# rasp_universal.net
KiCad netlist of a schematic drawn in EAGLE
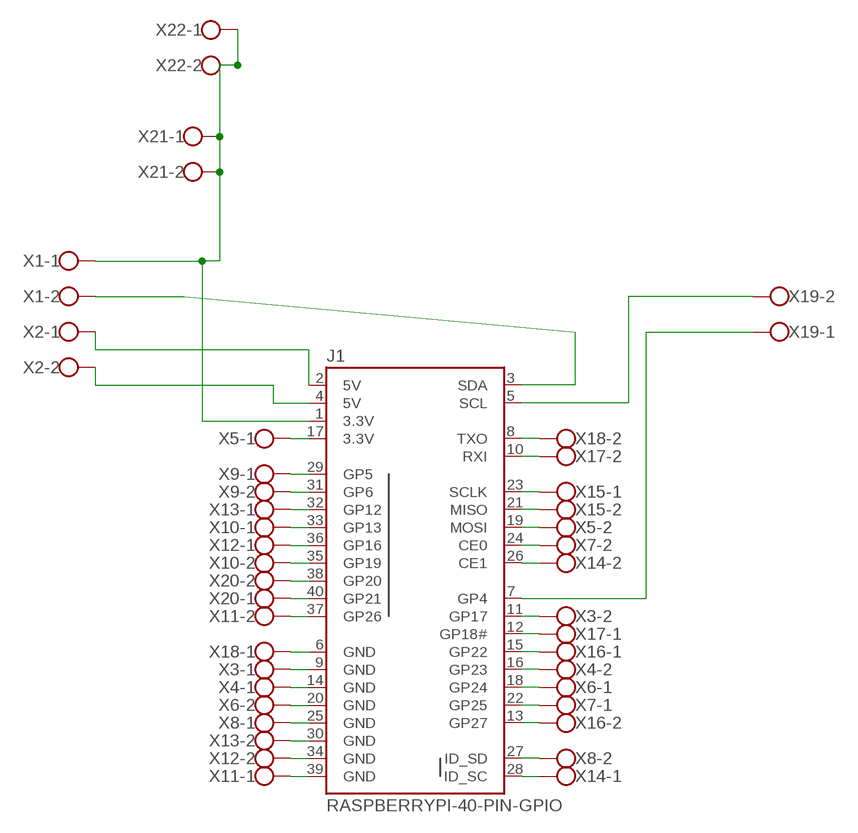
[diagram p0: schematic, sheet 1]

(export (version "E")
  (design (tool "Eeschema 10.0.6"))
  (components
    (comp (ref "J1")
      (value "RASPBERRYPI-40-PIN-GPIO")
      (footprint "eagle-import:2X20-SHROUDED")
      (libsource (lib "eagle-import") (part "RASPBERRYPI-40-PIN-GPIO"))
    )
    (comp (ref "X1")
      (value "W237-102")
      (footprint "eagle-import:W237-102")
      (fields (field (name "MPN") "237-102"))
      (libsource (lib "eagle-import") (part "W237-102"))
    )
    (comp (ref "X2")
      (value "W237-102")
      (footprint "eagle-import:W237-102")
      (fields (field (name "MPN") "237-102"))
      (libsource (lib "eagle-import") (part "W237-102"))
    )
    (comp (ref "X3")
      (value "W237-102")
      (footprint "eagle-import:W237-102")
      (fields (field (name "MPN") "237-102"))
      (libsource (lib "eagle-import") (part "W237-102"))
    )
    (comp (ref "X4")
      (value "W237-102")
      (footprint "eagle-import:W237-102")
      (fields (field (name "MPN") "237-102"))
      (libsource (lib "eagle-import") (part "W237-102"))
    )
    (comp (ref "X5")
      (value "W237-102")
      (footprint "eagle-import:W237-102")
      (fields (field (name "MPN") "237-102"))
      (libsource (lib "eagle-import") (part "W237-102"))
    )
    (comp (ref "X6")
      (value "W237-102")
      (footprint "eagle-import:W237-102")
      (fields (field (name "MPN") "237-102"))
      (libsource (lib "eagle-import") (part "W237-102"))
    )
    (comp (ref "X7")
      (value "W237-102")
      (footprint "eagle-import:W237-102")
      (fields (field (name "MPN") "237-102"))
      (libsource (lib "eagle-import") (part "W237-102"))
    )
    (comp (ref "X8")
      (value "W237-102")
      (footprint "eagle-import:W237-102")
      (fields (field (name "MPN") "237-102"))
      (libsource (lib "eagle-import") (part "W237-102"))
    )
    (comp (ref "X9")
      (value "W237-102")
      (footprint "eagle-import:W237-102")
      (fields (field (name "MPN") "237-102"))
      (libsource (lib "eagle-import") (part "W237-102"))
    )
    (comp (ref "X10")
      (value "W237-102")
      (footprint "eagle-import:W237-102")
      (fields (field (name "MPN") "237-102"))
      (libsource (lib "eagle-import") (part "W237-102"))
    )
    (comp (ref "X11")
      (value "W237-102")
      (footprint "eagle-import:W237-102")
      (fields (field (name "MPN") "237-102"))
      (libsource (lib "eagle-import") (part "W237-102"))
    )
    (comp (ref "X12")
      (value "W237-102")
      (footprint "eagle-import:W237-102")
      (fields (field (name "MPN") "237-102"))
      (libsource (lib "eagle-import") (part "W237-102"))
    )
    (comp (ref "X13")
      (value "W237-102")
      (footprint "eagle-import:W237-102")
      (fields (field (name "MPN") "237-102"))
      (libsource (lib "eagle-import") (part "W237-102"))
    )
    (comp (ref "X14")
      (value "W237-102")
      (footprint "eagle-import:W237-102")
      (fields (field (name "MPN") "237-102"))
      (libsource (lib "eagle-import") (part "W237-102"))
    )
    (comp (ref "X15")
      (value "W237-102")
      (footprint "eagle-import:W237-102")
      (fields (field (name "MPN") "237-102"))
      (libsource (lib "eagle-import") (part "W237-102"))
    )
    (comp (ref "X16")
      (value "W237-102")
      (footprint "eagle-import:W237-102")
      (fields (field (name "MPN") "237-102"))
      (libsource (lib "eagle-import") (part "W237-102"))
    )
    (comp (ref "X17")
      (value "W237-102")
      (footprint "eagle-import:W237-102")
      (fields (field (name "MPN") "237-102"))
      (libsource (lib "eagle-import") (part "W237-102"))
    )
    (comp (ref "X18")
      (value "W237-102")
      (footprint "eagle-import:W237-102")
      (fields (field (name "MPN") "237-102"))
      (libsource (lib "eagle-import") (part "W237-102"))
    )
    (comp (ref "X19")
      (value "W237-102")
      (footprint "eagle-import:W237-102")
      (fields (field (name "MPN") "237-102"))
      (libsource (lib "eagle-import") (part "W237-102"))
    )
    (comp (ref "X20")
      (value "W237-102")
      (footprint "eagle-import:W237-102")
      (fields (field (name "MPN") "237-102"))
      (libsource (lib "eagle-import") (part "W237-102"))
    )
    (comp (ref "X21")
      (value "W237-102")
      (footprint "eagle-import:W237-102")
      (fields (field (name "MPN") "237-102"))
      (libsource (lib "eagle-import") (part "W237-102"))
    )
    (comp (ref "X22")
      (value "W237-102")
      (footprint "eagle-import:W237-102")
      (fields (field (name "MPN") "237-102"))
      (libsource (lib "eagle-import") (part "W237-102"))
    )
  )
  (nets
    (net (code "1") (name "Net-(J1-CE0)") (class "Default")
      (node (ref "J1") (pin "24") (pinfunction "CE0_24") (pintype "output"))
      (node (ref "X7") (pin "2") (pinfunction "KL_2") (pintype "passive"))
    )
    (net (code "2") (name "Net-(J1-CE1)") (class "Default")
      (node (ref "J1") (pin "26") (pinfunction "CE1_26") (pintype "output"))
      (node (ref "X14") (pin "2") (pinfunction "KL_2") (pintype "passive"))
    )
    (net (code "3") (name "Net-(J1-GP4)") (class "Default")
      (node (ref "J1") (pin "7") (pinfunction "GP4_7") (pintype "bidirectional"))
      (node (ref "X19") (pin "1") (pinfunction "KL_1") (pintype "passive"))
    )
    (net (code "4") (name "Net-(J1-GP5)") (class "Default")
      (node (ref "J1") (pin "29") (pinfunction "GP5_29") (pintype "bidirectional"))
      (node (ref "X9") (pin "1") (pinfunction "KL_1") (pintype "passive"))
    )
    (net (code "5") (name "Net-(J1-GP6)") (class "Default")
      (node (ref "J1") (pin "31") (pinfunction "GP6_31") (pintype "bidirectional"))
      (node (ref "X9") (pin "2") (pinfunction "KL_2") (pintype "passive"))
    )
    (net (code "6") (name "Net-(J1-GP12)") (class "Default")
      (node (ref "J1") (pin "32") (pinfunction "GP12_32") (pintype "bidirectional"))
      (node (ref "X13") (pin "1") (pinfunction "KL_1") (pintype "passive"))
    )
    (net (code "7") (name "Net-(J1-GP13)") (class "Default")
      (node (ref "J1") (pin "33") (pinfunction "GP13_33") (pintype "bidirectional"))
      (node (ref "X10") (pin "1") (pinfunction "KL_1") (pintype "passive"))
    )
    (net (code "8") (name "Net-(J1-GP16)") (class "Default")
      (node (ref "J1") (pin "36") (pinfunction "GP16_36") (pintype "bidirectional"))
      (node (ref "X12") (pin "1") (pinfunction "KL_1") (pintype "passive"))
    )
    (net (code "9") (name "Net-(J1-GP17)") (class "Default")
      (node (ref "J1") (pin "11") (pinfunction "GP17_11") (pintype "bidirectional"))
      (node (ref "X3") (pin "2") (pinfunction "KL_2") (pintype "passive"))
    )
    (net (code "10") (name "Net-(J1-GP18#)") (class "Default")
      (node (ref "J1") (pin "12") (pinfunction "GP18#_12") (pintype "bidirectional"))
      (node (ref "X17") (pin "1") (pinfunction "KL_1") (pintype "passive"))
    )
    (net (code "11") (name "Net-(J1-GP19)") (class "Default")
      (node (ref "J1") (pin "35") (pinfunction "GP19_35") (pintype "bidirectional"))
      (node (ref "X10") (pin "2") (pinfunction "KL_2") (pintype "passive"))
    )
    (net (code "12") (name "Net-(J1-GP20)") (class "Default")
      (node (ref "J1") (pin "38") (pinfunction "GP20_38") (pintype "bidirectional"))
      (node (ref "X20") (pin "2") (pinfunction "KL_2") (pintype "passive"))
    )
    (net (code "13") (name "Net-(J1-GP21)") (class "Default")
      (node (ref "J1") (pin "40") (pinfunction "GP21_40") (pintype "bidirectional"))
      (node (ref "X20") (pin "1") (pinfunction "KL_1") (pintype "passive"))
    )
    (net (code "14") (name "Net-(J1-GP22)") (class "Default")
      (node (ref "J1") (pin "15") (pinfunction "GP22_15") (pintype "bidirectional"))
      (node (ref "X16") (pin "1") (pinfunction "KL_1") (pintype "passive"))
    )
    (net (code "15") (name "Net-(J1-GP23)") (class "Default")
      (node (ref "J1") (pin "16") (pinfunction "GP23_16") (pintype "bidirectional"))
      (node (ref "X4") (pin "2") (pinfunction "KL_2") (pintype "passive"))
    )
    (net (code "16") (name "Net-(J1-GP24)") (class "Default")
      (node (ref "J1") (pin "18") (pinfunction "GP24_18") (pintype "bidirectional"))
      (node (ref "X6") (pin "1") (pinfunction "KL_1") (pintype "passive"))
    )
    (net (code "17") (name "Net-(J1-GP25)") (class "Default")
      (node (ref "J1") (pin "22") (pinfunction "GP25_22") (pintype "bidirectional"))
      (node (ref "X7") (pin "1") (pinfunction "KL_1") (pintype "passive"))
    )
    (net (code "18") (name "Net-(J1-GP26)") (class "Default")
      (node (ref "J1") (pin "37") (pinfunction "GP26_37") (pintype "bidirectional"))
      (node (ref "X11") (pin "2") (pinfunction "KL_2") (pintype "passive"))
    )
    (net (code "19") (name "Net-(J1-GP27)") (class "Default")
      (node (ref "J1") (pin "13") (pinfunction "GP27_13") (pintype "bidirectional"))
      (node (ref "X16") (pin "2") (pinfunction "KL_2") (pintype "passive"))
    )
    (net (code "20") (name "Net-(J1-ID_SC)") (class "Default")
      (node (ref "J1") (pin "28") (pinfunction "ID_SC_28") (pintype "bidirectional"))
      (node (ref "X14") (pin "1") (pinfunction "KL_1") (pintype "passive"))
    )
    (net (code "21") (name "Net-(J1-ID_SD)") (class "Default")
      (node (ref "J1") (pin "27") (pinfunction "ID_SD_27") (pintype "bidirectional"))
      (node (ref "X8") (pin "2") (pinfunction "KL_2") (pintype "passive"))
    )
    (net (code "22") (name "Net-(J1-MISO)") (class "Default")
      (node (ref "J1") (pin "21") (pinfunction "MISO_21") (pintype "input"))
      (node (ref "X15") (pin "2") (pinfunction "KL_2") (pintype "passive"))
    )
    (net (code "23") (name "Net-(J1-MOSI)") (class "Default")
      (node (ref "J1") (pin "19") (pinfunction "MOSI_19") (pintype "output"))
      (node (ref "X5") (pin "2") (pinfunction "KL_2") (pintype "passive"))
    )
    (net (code "24") (name "Net-(J1-RXI)") (class "Default")
      (node (ref "J1") (pin "10") (pinfunction "RXI_10") (pintype "input"))
      (node (ref "X17") (pin "2") (pinfunction "KL_2") (pintype "passive"))
    )
    (net (code "25") (name "Net-(J1-SCL)") (class "Default")
      (node (ref "J1") (pin "5") (pinfunction "SCL_5") (pintype "bidirectional"))
      (node (ref "X19") (pin "2") (pinfunction "KL_2") (pintype "passive"))
    )
    (net (code "26") (name "Net-(J1-SCLK)") (class "Default")
      (node (ref "J1") (pin "23") (pinfunction "SCLK_23") (pintype "output"))
      (node (ref "X15") (pin "1") (pinfunction "KL_1") (pintype "passive"))
    )
    (net (code "27") (name "Net-(J1-SDA)") (class "Default")
      (node (ref "J1") (pin "3") (pinfunction "SDA_3") (pintype "bidirectional"))
      (node (ref "X1") (pin "2") (pinfunction "KL_2") (pintype "passive"))
    )
    (net (code "28") (name "Net-(J1-TXO)") (class "Default")
      (node (ref "J1") (pin "8") (pinfunction "TXO_8") (pintype "output"))
      (node (ref "X18") (pin "2") (pinfunction "KL_2") (pintype "passive"))
    )
    (net (code "29") (name "Net-(X1A-KL)") (class "Default")
      (node (ref "J1") (pin "1") (pinfunction "3.3V_1") (pintype "power_in"))
      (node (ref "X1") (pin "1") (pinfunction "KL_1") (pintype "passive"))
      (node (ref "X21") (pin "1") (pinfunction "KL_1") (pintype "passive"))
      (node (ref "X21") (pin "2") (pinfunction "KL_2") (pintype "passive"))
      (node (ref "X22") (pin "1") (pinfunction "KL_1") (pintype "passive"))
      (node (ref "X22") (pin "2") (pinfunction "KL_2") (pintype "passive"))
    )
    (net (code "30") (name "Net-(X2A-KL)") (class "Default")
      (node (ref "J1") (pin "2") (pinfunction "5V_2") (pintype "power_in"))
      (node (ref "X2") (pin "1") (pinfunction "KL_1") (pintype "passive"))
    )
    (net (code "31") (name "Net-(X2B-KL)") (class "Default")
      (node (ref "J1") (pin "4") (pinfunction "5V_4") (pintype "power_in"))
      (node (ref "X2") (pin "2") (pinfunction "KL_2") (pintype "passive"))
    )
    (net (code "32") (name "Net-(X3A-KL)") (class "Default")
      (node (ref "J1") (pin "9") (pinfunction "GND_9") (pintype "power_in"))
      (node (ref "X3") (pin "1") (pinfunction "KL_1") (pintype "passive"))
    )
    (net (code "33") (name "Net-(X4A-KL)") (class "Default")
      (node (ref "J1") (pin "14") (pinfunction "GND_14") (pintype "power_in"))
      (node (ref "X4") (pin "1") (pinfunction "KL_1") (pintype "passive"))
    )
    (net (code "34") (name "Net-(X5A-KL)") (class "Default")
      (node (ref "J1") (pin "17") (pinfunction "3.3V_17") (pintype "power_in"))
      (node (ref "X5") (pin "1") (pinfunction "KL_1") (pintype "passive"))
    )
    (net (code "35") (name "Net-(X6B-KL)") (class "Default")
      (node (ref "J1") (pin "20") (pinfunction "GND_20") (pintype "power_in"))
      (node (ref "X6") (pin "2") (pinfunction "KL_2") (pintype "passive"))
    )
    (net (code "36") (name "Net-(X8A-KL)") (class "Default")
      (node (ref "J1") (pin "25") (pinfunction "GND_25") (pintype "power_in"))
      (node (ref "X8") (pin "1") (pinfunction "KL_1") (pintype "passive"))
    )
    (net (code "37") (name "Net-(X11A-KL)") (class "Default")
      (node (ref "J1") (pin "39") (pinfunction "GND_39") (pintype "power_in"))
      (node (ref "X11") (pin "1") (pinfunction "KL_1") (pintype "passive"))
    )
    (net (code "38") (name "Net-(X12B-KL)") (class "Default")
      (node (ref "J1") (pin "34") (pinfunction "GND_34") (pintype "power_in"))
      (node (ref "X12") (pin "2") (pinfunction "KL_2") (pintype "passive"))
    )
    (net (code "39") (name "Net-(X13B-KL)") (class "Default")
      (node (ref "J1") (pin "30") (pinfunction "GND_30") (pintype "power_in"))
      (node (ref "X13") (pin "2") (pinfunction "KL_2") (pintype "passive"))
    )
    (net (code "40") (name "Net-(X18A-KL)") (class "Default")
      (node (ref "J1") (pin "6") (pinfunction "GND_6") (pintype "power_in"))
      (node (ref "X18") (pin "1") (pinfunction "KL_1") (pintype "passive"))
    )
  )
)
